# PowerBrickBoard.net
KiCad netlist of a schematic drawn in EAGLE
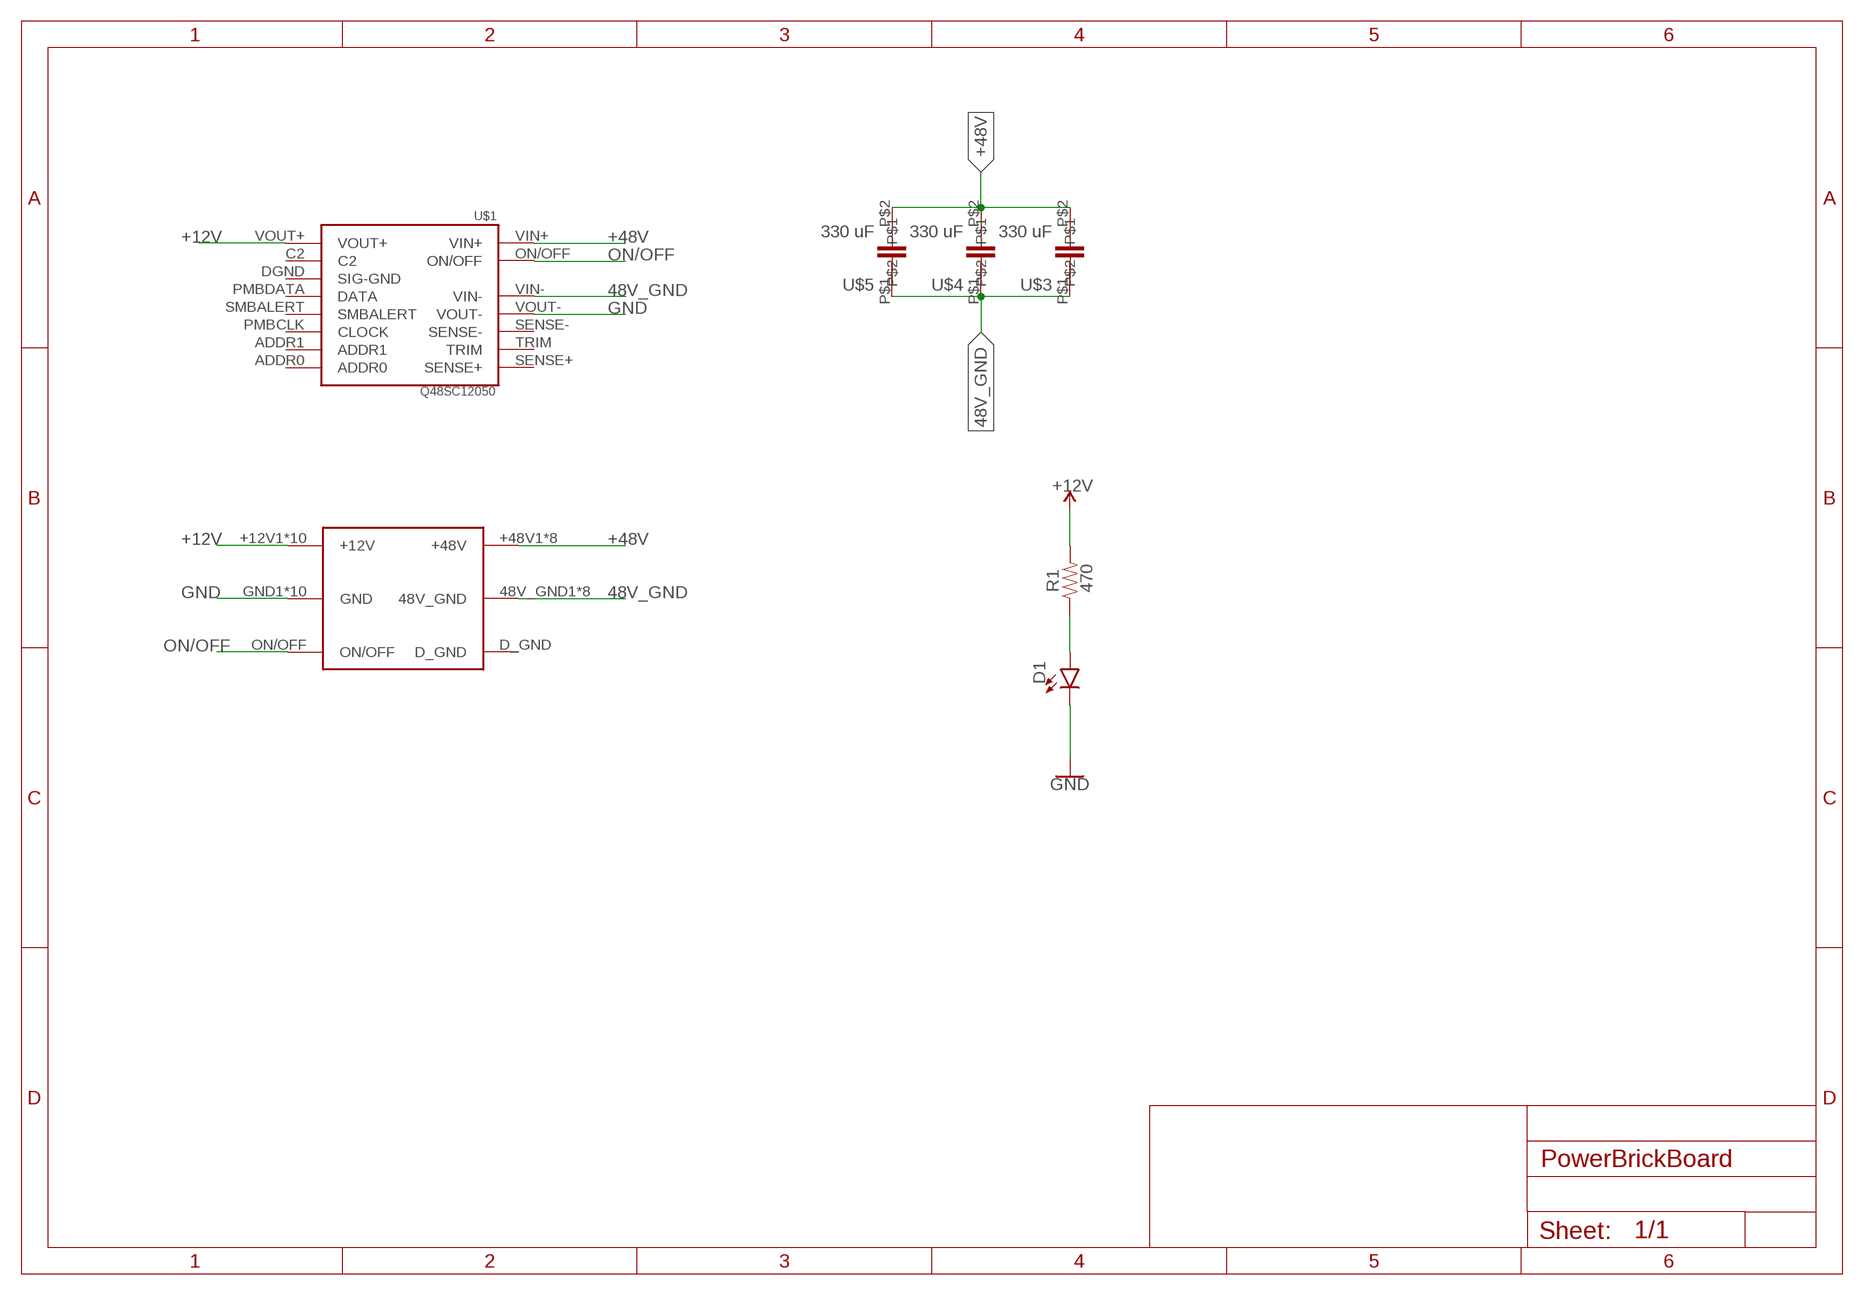
[diagram p0: schematic, sheet 1]

(export (version "E")
  (design (tool "Eeschema 10.0.6"))
  (components
    (comp (ref "D1")
      (value "LED0603")
      (footprint "eagle-import:LED-0603")
      (libsource (lib "eagle-import") (part "LED0603"))
    )
    (comp (ref "R1")
      (value "470")
      (footprint "eagle-import:0603")
      (libsource (lib "eagle-import") (part "RESISTOR0603"))
    )
    (comp (ref "U$1")
      (value "Q48SC12050")
      (footprint "eagle-import:Q48SC12050")
      (libsource (lib "eagle-import") (part "Q48SC12050"))
    )
    (comp (ref "U$2")
      (value "BRICK_TO_POWER_DIST_WHOLE")
      (footprint "eagle-import:BRICK_TO_POWER_DIST_WHOLE")
      (libsource (lib "eagle-import") (part "BRICK_TO_POWER_DIST_WHOLE"))
    )
    (comp (ref "U$3")
      (value "330 uF")
      (footprint "eagle-import:UCM1H331MNL1GS")
      (libsource (lib "eagle-import") (part "UCM1H331MNL1GS"))
    )
    (comp (ref "U$4")
      (value "330 uF")
      (footprint "eagle-import:UCM1H331MNL1GS")
      (libsource (lib "eagle-import") (part "UCM1H331MNL1GS"))
    )
    (comp (ref "U$5")
      (value "330 uF")
      (footprint "eagle-import:UCM1H331MNL1GS")
      (libsource (lib "eagle-import") (part "UCM1H331MNL1GS"))
    )
  )
  (nets
    (net (code "1") (name "+48V") (class "Default")
      (node (ref "U$1") (pin "VIN+") (pinfunction "VIN+_VIN+") (pintype "bidirectional"))
      (node (ref "U$2") (pin "+48V1") (pinfunction "+48V_+48V1") (pintype "bidirectional"))
      (node (ref "U$2") (pin "+48V2") (pinfunction "+48V_+48V2") (pintype "bidirectional"))
      (node (ref "U$2") (pin "+48V3") (pinfunction "+48V_+48V3") (pintype "bidirectional"))
      (node (ref "U$2") (pin "+48V4") (pinfunction "+48V_+48V4") (pintype "bidirectional"))
      (node (ref "U$2") (pin "+48V5") (pinfunction "+48V_+48V5") (pintype "bidirectional"))
      (node (ref "U$2") (pin "+48V6") (pinfunction "+48V_+48V6") (pintype "bidirectional"))
      (node (ref "U$2") (pin "+48V7") (pinfunction "+48V_+48V7") (pintype "bidirectional"))
      (node (ref "U$2") (pin "+48V8") (pinfunction "+48V_+48V8") (pintype "bidirectional"))
      (node (ref "U$3") (pin "P$2") (pinfunction "P$2_P$2") (pintype "bidirectional"))
      (node (ref "U$4") (pin "P$2") (pinfunction "P$2_P$2") (pintype "bidirectional"))
      (node (ref "U$5") (pin "P$2") (pinfunction "P$2_P$2") (pintype "bidirectional"))
    )
    (net (code "2") (name "/ON{slash}OFF") (class "Default")
      (node (ref "U$1") (pin "ON/OFF") (pinfunction "ON/OFF_ON/OFF") (pintype "bidirectional"))
      (node (ref "U$2") (pin "ON/OFF") (pinfunction "ON/OFF_ON/OFF") (pintype "bidirectional"))
    )
    (net (code "3") (name "48V_GND") (class "Default")
      (node (ref "U$1") (pin "VIN-") (pinfunction "VIN-_VIN-") (pintype "bidirectional"))
      (node (ref "U$2") (pin "48V_GND1") (pinfunction "48V_GND_48V_GND1") (pintype "bidirectional"))
      (node (ref "U$2") (pin "48V_GND2") (pinfunction "48V_GND_48V_GND2") (pintype "bidirectional"))
      (node (ref "U$2") (pin "48V_GND3") (pinfunction "48V_GND_48V_GND3") (pintype "bidirectional"))
      (node (ref "U$2") (pin "48V_GND4") (pinfunction "48V_GND_48V_GND4") (pintype "bidirectional"))
      (node (ref "U$2") (pin "48V_GND5") (pinfunction "48V_GND_48V_GND5") (pintype "bidirectional"))
      (node (ref "U$2") (pin "48V_GND6") (pinfunction "48V_GND_48V_GND6") (pintype "bidirectional"))
      (node (ref "U$2") (pin "48V_GND7") (pinfunction "48V_GND_48V_GND7") (pintype "bidirectional"))
      (node (ref "U$2") (pin "48V_GND8") (pinfunction "48V_GND_48V_GND8") (pintype "bidirectional"))
      (node (ref "U$3") (pin "P$1") (pinfunction "P$1_P$1") (pintype "bidirectional"))
      (node (ref "U$4") (pin "P$1") (pinfunction "P$1_P$1") (pintype "bidirectional"))
      (node (ref "U$5") (pin "P$1") (pinfunction "P$1_P$1") (pintype "bidirectional"))
    )
    (net (code "4") (name "GND") (class "Default")
      (node (ref "D1") (pin "C") (pinfunction "C_C") (pintype "passive"))
      (node (ref "U$1") (pin "VOUT-") (pinfunction "VOUT-_VOUT-") (pintype "bidirectional"))
      (node (ref "U$2") (pin "GND1") (pinfunction "GND_GND1") (pintype "bidirectional"))
      (node (ref "U$2") (pin "GND10") (pinfunction "GND_GND10") (pintype "bidirectional"))
      (node (ref "U$2") (pin "GND2") (pinfunction "GND_GND2") (pintype "bidirectional"))
      (node (ref "U$2") (pin "GND3") (pinfunction "GND_GND3") (pintype "bidirectional"))
      (node (ref "U$2") (pin "GND4") (pinfunction "GND_GND4") (pintype "bidirectional"))
      (node (ref "U$2") (pin "GND5") (pinfunction "GND_GND5") (pintype "bidirectional"))
      (node (ref "U$2") (pin "GND6") (pinfunction "GND_GND6") (pintype "bidirectional"))
      (node (ref "U$2") (pin "GND7") (pinfunction "GND_GND7") (pintype "bidirectional"))
      (node (ref "U$2") (pin "GND8") (pinfunction "GND_GND8") (pintype "bidirectional"))
      (node (ref "U$2") (pin "GND9") (pinfunction "GND_GND9") (pintype "bidirectional"))
    )
    (net (code "5") (name "Net-(D1-PadA)") (class "Default")
      (node (ref "D1") (pin "A") (pinfunction "A_A") (pintype "passive"))
      (node (ref "R1") (pin "1") (pinfunction "1_1") (pintype "passive"))
    )
    (net (code "6") (name "VCC") (class "Default")
      (node (ref "R1") (pin "2") (pinfunction "2_2") (pintype "passive"))
      (node (ref "U$1") (pin "VOUT+") (pinfunction "VOUT+_VOUT+") (pintype "bidirectional"))
      (node (ref "U$2") (pin "+12V1") (pinfunction "+12V_+12V1") (pintype "bidirectional"))
      (node (ref "U$2") (pin "+12V10") (pinfunction "+12V_+12V10") (pintype "bidirectional"))
      (node (ref "U$2") (pin "+12V2") (pinfunction "+12V_+12V2") (pintype "bidirectional"))
      (node (ref "U$2") (pin "+12V3") (pinfunction "+12V_+12V3") (pintype "bidirectional"))
      (node (ref "U$2") (pin "+12V4") (pinfunction "+12V_+12V4") (pintype "bidirectional"))
      (node (ref "U$2") (pin "+12V5") (pinfunction "+12V_+12V5") (pintype "bidirectional"))
      (node (ref "U$2") (pin "+12V6") (pinfunction "+12V_+12V6") (pintype "bidirectional"))
      (node (ref "U$2") (pin "+12V7") (pinfunction "+12V_+12V7") (pintype "bidirectional"))
      (node (ref "U$2") (pin "+12V8") (pinfunction "+12V_+12V8") (pintype "bidirectional"))
      (node (ref "U$2") (pin "+12V9") (pinfunction "+12V_+12V9") (pintype "bidirectional"))
    )
    (net (code "7") (name "unconnected-(U$1-CLOCK-PadPMBCLK)") (class "Default")
      (node (ref "U$1") (pin "PMBCLK") (pinfunction "CLOCK_PMBCLK") (pintype "bidirectional"))
    )
    (net (code "8") (name "unconnected-(U$1-DATA-PadPMBDATA)") (class "Default")
      (node (ref "U$1") (pin "PMBDATA") (pinfunction "DATA_PMBDATA") (pintype "bidirectional"))
    )
    (net (code "9") (name "unconnected-(U$1-PadADDR0)") (class "Default")
      (node (ref "U$1") (pin "ADDR0") (pinfunction "ADDR0_ADDR0") (pintype "bidirectional"))
    )
    (net (code "10") (name "unconnected-(U$1-PadADDR1)") (class "Default")
      (node (ref "U$1") (pin "ADDR1") (pinfunction "ADDR1_ADDR1") (pintype "bidirectional"))
    )
    (net (code "11") (name "unconnected-(U$1-PadC2)") (class "Default")
      (node (ref "U$1") (pin "C2") (pinfunction "C2_C2") (pintype "bidirectional"))
    )
    (net (code "12") (name "unconnected-(U$1-PadSENSE+)") (class "Default")
      (node (ref "U$1") (pin "SENSE+") (pinfunction "SENSE+_SENSE+") (pintype "bidirectional"))
    )
    (net (code "13") (name "unconnected-(U$1-PadSENSE-)") (class "Default")
      (node (ref "U$1") (pin "SENSE-") (pinfunction "SENSE-_SENSE-") (pintype "bidirectional"))
    )
    (net (code "14") (name "unconnected-(U$1-PadSMBALERT)") (class "Default")
      (node (ref "U$1") (pin "SMBALERT") (pinfunction "SMBALERT_SMBALERT") (pintype "bidirectional"))
    )
    (net (code "15") (name "unconnected-(U$1-PadTRIM)") (class "Default")
      (node (ref "U$1") (pin "TRIM") (pinfunction "TRIM_TRIM") (pintype "bidirectional"))
    )
    (net (code "16") (name "unconnected-(U$1-SIG-GND-PadDGND)") (class "Default")
      (node (ref "U$1") (pin "DGND") (pinfunction "SIG-GND_DGND") (pintype "bidirectional"))
    )
    (net (code "17") (name "unconnected-(U$2-PadD_GND)") (class "Default")
      (node (ref "U$2") (pin "D_GND") (pinfunction "D_GND_D_GND") (pintype "bidirectional"))
    )
  )
)
